# mini-rfsynth.net
KiCad netlist of a schematic drawn in Altium Designer
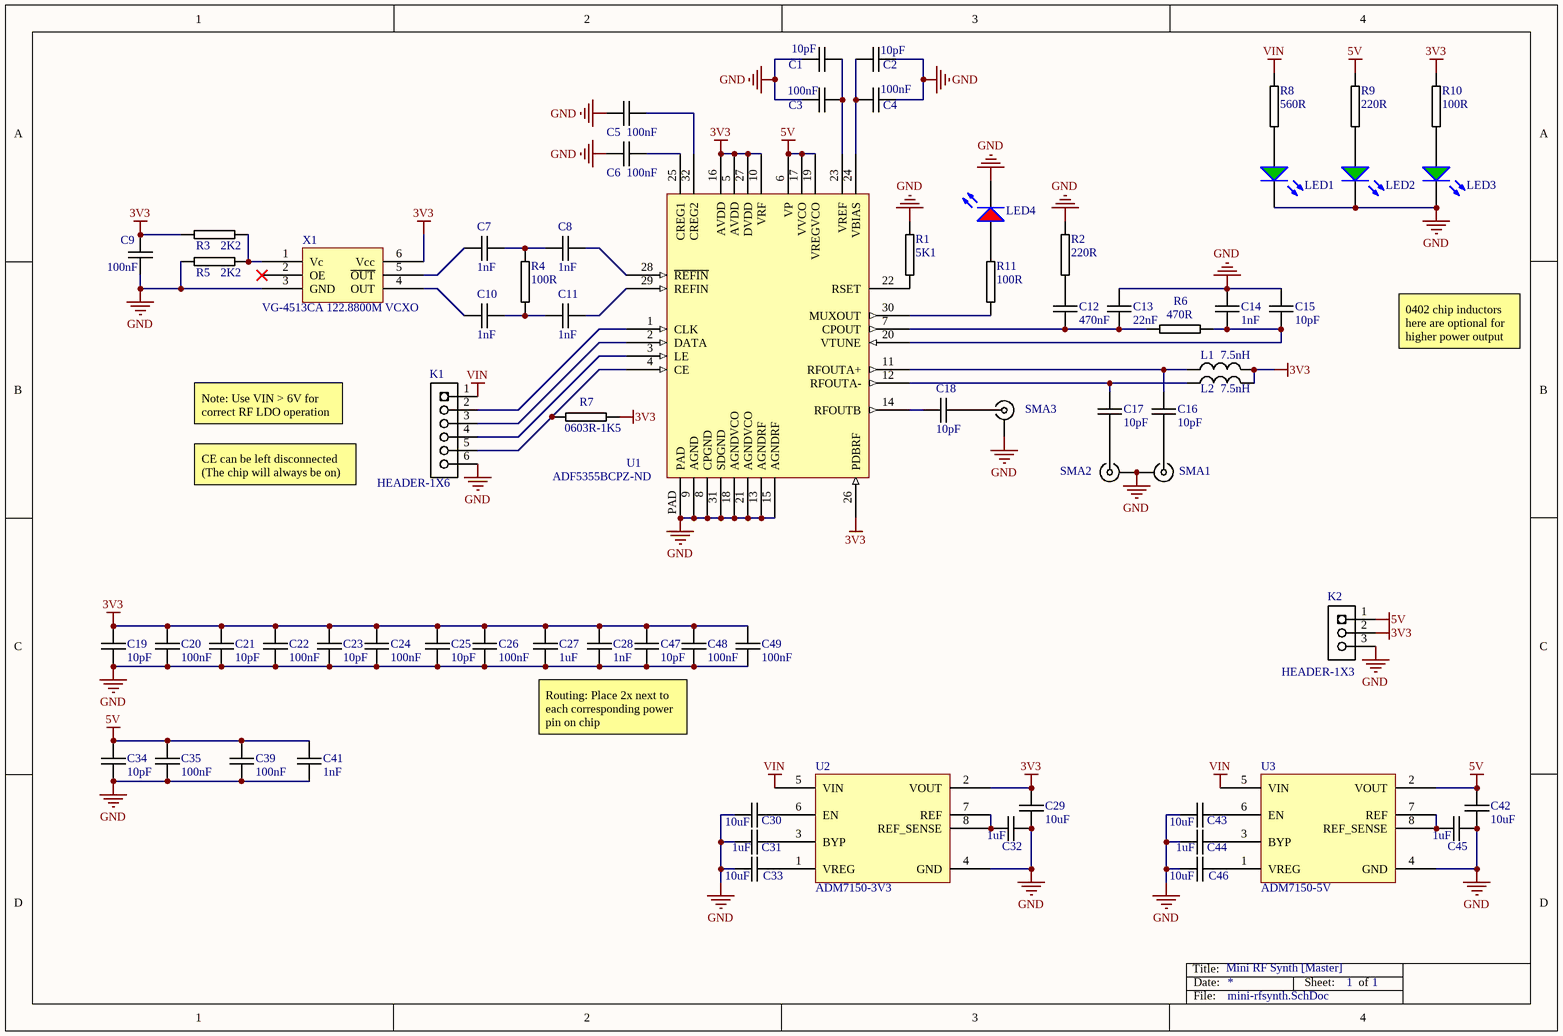
[diagram p0: mini-rfsynth.SchDoc]

(export (version "E")
  (design (tool "Eeschema 10.0.6"))
  (components
    (comp (ref "C1")
      (value "10pF")
      (footprint "0603C-GENERIC")
      (description "CAPACITOR 0603 CERAMIC")
      (libsource (lib "SMD Capacitors 0603") (part "0603C-10PF-50V-C0G-MUR"))
    )
    (comp (ref "C2")
      (value "10pF")
      (footprint "0603C-GENERIC")
      (description "CAPACITOR 0603 CERAMIC")
      (libsource (lib "SMD Capacitors 0603") (part "0603C-10PF-50V-C0G-MUR"))
    )
    (comp (ref "C3")
      (value "100nF")
      (footprint "0603C-GENERIC")
      (description "CAPACITOR 0603 CERAMIC")
      (fields (field (name "TOLERANCE") "±10%") (field (name "MANUFACTURER PART NUMBER") "C1608X7R1H103K"))
      (libsource (lib "SMD Capacitors 0603") (part "0603C-100NF-50V-X7R-TDK"))
    )
    (comp (ref "C4")
      (value "100nF")
      (footprint "0603C-GENERIC")
      (description "CAPACITOR 0603 CERAMIC")
      (fields (field (name "TOLERANCE") "±10%") (field (name "MANUFACTURER PART NUMBER") "C1608X7R1H103K"))
      (libsource (lib "SMD Capacitors 0603") (part "0603C-100NF-50V-X7R-TDK"))
    )
    (comp (ref "C5")
      (value "100nF")
      (footprint "0603C-GENERIC")
      (description "CAPACITOR 0603 CERAMIC")
      (fields (field (name "TOLERANCE") "±10%") (field (name "MANUFACTURER PART NUMBER") "C1608X7R1H103K"))
      (libsource (lib "SMD Capacitors 0603") (part "0603C-100NF-50V-X7R-TDK"))
    )
    (comp (ref "C6")
      (value "100nF")
      (footprint "0603C-GENERIC")
      (description "CAPACITOR 0603 CERAMIC")
      (fields (field (name "TOLERANCE") "±10%") (field (name "MANUFACTURER PART NUMBER") "C1608X7R1H103K"))
      (libsource (lib "SMD Capacitors 0603") (part "0603C-100NF-50V-X7R-TDK"))
    )
    (comp (ref "C7")
      (value "1nF")
      (footprint "0603C-GENERIC")
      (description "CAPACITOR 0603 CERAMIC")
      (libsource (lib "SMD Capacitors 0603") (part "0603C-1NF-50V-X7R"))
    )
    (comp (ref "C8")
      (value "1nF")
      (footprint "0603C-GENERIC")
      (description "CAPACITOR 0603 CERAMIC")
      (libsource (lib "SMD Capacitors 0603") (part "0603C-1NF-50V-X7R"))
    )
    (comp (ref "C9")
      (value "100nF")
      (footprint "0603C-GENERIC")
      (description "CAPACITOR 0603 CERAMIC")
      (fields (field (name "TOLERANCE") "±10%") (field (name "MANUFACTURER PART NUMBER") "C1608X7R1H103K"))
      (libsource (lib "SMD Capacitors 0603") (part "0603C-100NF-50V-X7R-TDK"))
    )
    (comp (ref "C10")
      (value "1nF")
      (footprint "0603C-GENERIC")
      (description "CAPACITOR 0603 CERAMIC")
      (libsource (lib "SMD Capacitors 0603") (part "0603C-1NF-50V-X7R"))
    )
    (comp (ref "C11")
      (value "1nF")
      (footprint "0603C-GENERIC")
      (description "CAPACITOR 0603 CERAMIC")
      (libsource (lib "SMD Capacitors 0603") (part "0603C-1NF-50V-X7R"))
    )
    (comp (ref "C12")
      (value "470nF")
      (footprint "0603C-GENERIC")
      (description "CAPACITOR 0603 CERAMIC")
      (fields
        (field (name "MANUFACTURER") "Murata Electronics North America")
        (field (name "TOLERANCE") "±10%")
      )
      (libsource (lib "SMD Capacitors 0603") (part "0603C-470NF-25V-X7R-MUR"))
    )
    (comp (ref "C13")
      (value "22nF")
      (footprint "0603C-GENERIC")
      (description "CAPACITOR 0603 CERAMIC")
      (libsource (lib "SMD Capacitors 0603") (part "0603C-22NF-50V-X7R-TDK"))
    )
    (comp (ref "C14")
      (value "1nF")
      (footprint "0603C-GENERIC")
      (description "CAPACITOR 0603 CERAMIC")
      (libsource (lib "SMD Capacitors 0603") (part "0603C-1NF-50V-X7R"))
    )
    (comp (ref "C15")
      (value "10pF")
      (footprint "0603C-GENERIC")
      (description "CAPACITOR 0603 CERAMIC")
      (libsource (lib "SMD Capacitors 0603") (part "0603C-10PF-50V-C0G-MUR"))
    )
    (comp (ref "C16")
      (value "10pF")
      (footprint "0603C-GENERIC")
      (description "CAPACITOR 0603 CERAMIC")
      (libsource (lib "SMD Capacitors 0603") (part "0603C-10PF-50V-C0G-MUR"))
    )
    (comp (ref "C17")
      (value "10pF")
      (footprint "0603C-GENERIC")
      (description "CAPACITOR 0603 CERAMIC")
      (libsource (lib "SMD Capacitors 0603") (part "0603C-10PF-50V-C0G-MUR"))
    )
    (comp (ref "C18")
      (value "10pF")
      (footprint "0603C-GENERIC")
      (description "CAPACITOR 0603 CERAMIC")
      (libsource (lib "SMD Capacitors 0603") (part "0603C-10PF-50V-C0G-MUR"))
    )
    (comp (ref "C19")
      (value "10pF")
      (footprint "0603C-GENERIC")
      (description "CAPACITOR 0603 CERAMIC")
      (libsource (lib "SMD Capacitors 0603") (part "0603C-10PF-50V-C0G-MUR"))
    )
    (comp (ref "C20")
      (value "100nF")
      (footprint "0603C-GENERIC")
      (description "CAPACITOR 0603 CERAMIC")
      (fields (field (name "TOLERANCE") "±10%") (field (name "MANUFACTURER PART NUMBER") "C1608X7R1H103K"))
      (libsource (lib "SMD Capacitors 0603") (part "0603C-100NF-50V-X7R-TDK"))
    )
    (comp (ref "C21")
      (value "10pF")
      (footprint "0603C-GENERIC")
      (description "CAPACITOR 0603 CERAMIC")
      (libsource (lib "SMD Capacitors 0603") (part "0603C-10PF-50V-C0G-MUR"))
    )
    (comp (ref "C22")
      (value "100nF")
      (footprint "0603C-GENERIC")
      (description "CAPACITOR 0603 CERAMIC")
      (fields (field (name "TOLERANCE") "±10%") (field (name "MANUFACTURER PART NUMBER") "C1608X7R1H103K"))
      (libsource (lib "SMD Capacitors 0603") (part "0603C-100NF-50V-X7R-TDK"))
    )
    (comp (ref "C23")
      (value "10pF")
      (footprint "0603C-GENERIC")
      (description "CAPACITOR 0603 CERAMIC")
      (libsource (lib "SMD Capacitors 0603") (part "0603C-10PF-50V-C0G-MUR"))
    )
    (comp (ref "C24")
      (value "100nF")
      (footprint "0603C-GENERIC")
      (description "CAPACITOR 0603 CERAMIC")
      (fields (field (name "TOLERANCE") "±10%") (field (name "MANUFACTURER PART NUMBER") "C1608X7R1H103K"))
      (libsource (lib "SMD Capacitors 0603") (part "0603C-100NF-50V-X7R-TDK"))
    )
    (comp (ref "C25")
      (value "10pF")
      (footprint "0603C-GENERIC")
      (description "CAPACITOR 0603 CERAMIC")
      (libsource (lib "SMD Capacitors 0603") (part "0603C-10PF-50V-C0G-MUR"))
    )
    (comp (ref "C26")
      (value "100nF")
      (footprint "0603C-GENERIC")
      (description "CAPACITOR 0603 CERAMIC")
      (fields (field (name "TOLERANCE") "±10%") (field (name "MANUFACTURER PART NUMBER") "C1608X7R1H103K"))
      (libsource (lib "SMD Capacitors 0603") (part "0603C-100NF-50V-X7R-TDK"))
    )
    (comp (ref "C27")
      (value "1uF")
      (footprint "0603C-GENERIC")
      (description "CAPACITOR 0603 CERAMIC")
      (fields
        (field (name "MANUFACTURER PART NUMBER") "EMK107B7105KA-T")
        (field (name "MANUFACTURER") "Taiyo Yuden")
      )
      (libsource (lib "SMD Capacitors 0603") (part "0603C-1UF-16V-X7R-TAY"))
    )
    (comp (ref "C28")
      (value "1nF")
      (footprint "0603C-GENERIC")
      (description "CAPACITOR 0603 CERAMIC")
      (libsource (lib "SMD Capacitors 0603") (part "0603C-1NF-50V-X7R"))
    )
    (comp (ref "C29")
      (value "10uF")
      (footprint "0805C-GENERIC")
      (description "CAPACITOR 0805 CERAMIC")
      (fields
        (field (name "MANUFACTURER PART NUMBER") "C2012X5R1C106M")
        (field (name "MANUFACTURER") "TDK Corporation")
      )
      (libsource (lib "SMD Capacitors 0805") (part "0805C-10UF-16V-X5R-TDK"))
    )
    (comp (ref "C30")
      (value "10uF")
      (footprint "0805C-GENERIC")
      (description "CAPACITOR 0805 CERAMIC")
      (fields
        (field (name "MANUFACTURER PART NUMBER") "C2012X5R1C106M")
        (field (name "MANUFACTURER") "TDK Corporation")
      )
      (libsource (lib "SMD Capacitors 0805") (part "0805C-10UF-16V-X5R-TDK"))
    )
    (comp (ref "C31")
      (value "1uF")
      (footprint "0603C-GENERIC")
      (description "CAPACITOR 0603 CERAMIC")
      (fields
        (field (name "MANUFACTURER PART NUMBER") "EMK107B7105KA-T")
        (field (name "MANUFACTURER") "Taiyo Yuden")
      )
      (libsource (lib "SMD Capacitors 0603") (part "0603C-1UF-16V-X7R-TAY"))
    )
    (comp (ref "C32")
      (value "1uF")
      (footprint "0603C-GENERIC")
      (description "CAPACITOR 0603 CERAMIC")
      (fields
        (field (name "MANUFACTURER PART NUMBER") "EMK107B7105KA-T")
        (field (name "MANUFACTURER") "Taiyo Yuden")
      )
      (libsource (lib "SMD Capacitors 0603") (part "0603C-1UF-16V-X7R-TAY"))
    )
    (comp (ref "C33")
      (value "10uF")
      (footprint "0805C-GENERIC")
      (description "CAPACITOR 0805 CERAMIC")
      (fields
        (field (name "MANUFACTURER PART NUMBER") "C2012X5R1C106M")
        (field (name "MANUFACTURER") "TDK Corporation")
      )
      (libsource (lib "SMD Capacitors 0805") (part "0805C-10UF-16V-X5R-TDK"))
    )
    (comp (ref "C34")
      (value "10pF")
      (footprint "0603C-GENERIC")
      (description "CAPACITOR 0603 CERAMIC")
      (libsource (lib "SMD Capacitors 0603") (part "0603C-10PF-50V-C0G-MUR"))
    )
    (comp (ref "C35")
      (value "100nF")
      (footprint "0603C-GENERIC")
      (description "CAPACITOR 0603 CERAMIC")
      (fields (field (name "TOLERANCE") "±10%") (field (name "MANUFACTURER PART NUMBER") "C1608X7R1H103K"))
      (libsource (lib "SMD Capacitors 0603") (part "0603C-100NF-50V-X7R-TDK"))
    )
    (comp (ref "C39")
      (value "100nF")
      (footprint "0603C-GENERIC")
      (description "CAPACITOR 0603 CERAMIC")
      (fields (field (name "TOLERANCE") "±10%") (field (name "MANUFACTURER PART NUMBER") "C1608X7R1H103K"))
      (libsource (lib "SMD Capacitors 0603") (part "0603C-100NF-50V-X7R-TDK"))
    )
    (comp (ref "C41")
      (value "1nF")
      (footprint "0603C-GENERIC")
      (description "CAPACITOR 0603 CERAMIC")
      (libsource (lib "SMD Capacitors 0603") (part "0603C-1NF-50V-X7R"))
    )
    (comp (ref "C42")
      (value "10uF")
      (footprint "0805C-GENERIC")
      (description "CAPACITOR 0805 CERAMIC")
      (fields
        (field (name "MANUFACTURER PART NUMBER") "C2012X5R1C106M")
        (field (name "MANUFACTURER") "TDK Corporation")
      )
      (libsource (lib "SMD Capacitors 0805") (part "0805C-10UF-16V-X5R-TDK"))
    )
    (comp (ref "C43")
      (value "10uF")
      (footprint "0805C-GENERIC")
      (description "CAPACITOR 0805 CERAMIC")
      (fields
        (field (name "MANUFACTURER PART NUMBER") "C2012X5R1C106M")
        (field (name "MANUFACTURER") "TDK Corporation")
      )
      (libsource (lib "SMD Capacitors 0805") (part "0805C-10UF-16V-X5R-TDK"))
    )
    (comp (ref "C44")
      (value "1uF")
      (footprint "0603C-GENERIC")
      (description "CAPACITOR 0603 CERAMIC")
      (fields
        (field (name "MANUFACTURER PART NUMBER") "EMK107B7105KA-T")
        (field (name "MANUFACTURER") "Taiyo Yuden")
      )
      (libsource (lib "SMD Capacitors 0603") (part "0603C-1UF-16V-X7R-TAY"))
    )
    (comp (ref "C45")
      (value "1uF")
      (footprint "0603C-GENERIC")
      (description "CAPACITOR 0603 CERAMIC")
      (fields
        (field (name "MANUFACTURER PART NUMBER") "EMK107B7105KA-T")
        (field (name "MANUFACTURER") "Taiyo Yuden")
      )
      (libsource (lib "SMD Capacitors 0603") (part "0603C-1UF-16V-X7R-TAY"))
    )
    (comp (ref "C46")
      (value "10uF")
      (footprint "0805C-GENERIC")
      (description "CAPACITOR 0805 CERAMIC")
      (fields
        (field (name "MANUFACTURER PART NUMBER") "C2012X5R1C106M")
        (field (name "MANUFACTURER") "TDK Corporation")
      )
      (libsource (lib "SMD Capacitors 0805") (part "0805C-10UF-16V-X5R-TDK"))
    )
    (comp (ref "C47")
      (value "10pF")
      (footprint "0603C-GENERIC")
      (description "CAPACITOR 0603 CERAMIC")
      (libsource (lib "SMD Capacitors 0603") (part "0603C-10PF-50V-C0G-MUR"))
    )
    (comp (ref "C48")
      (value "100nF")
      (footprint "0603C-GENERIC")
      (description "CAPACITOR 0603 CERAMIC")
      (fields (field (name "TOLERANCE") "±10%") (field (name "MANUFACTURER PART NUMBER") "C1608X7R1H103K"))
      (libsource (lib "SMD Capacitors 0603") (part "0603C-100NF-50V-X7R-TDK"))
    )
    (comp (ref "C49")
      (value "100nF")
      (footprint "0603C-GENERIC")
      (description "CAPACITOR 0603 CERAMIC")
      (fields (field (name "TOLERANCE") "±10%") (field (name "MANUFACTURER PART NUMBER") "C1608X7R1H103K"))
      (libsource (lib "SMD Capacitors 0603") (part "0603C-100NF-50V-X7R-TDK"))
    )
    (comp (ref "K1")
      (value "HEADER-1X6")
      (footprint "HEADER-1X6")
      (libsource (lib "TH Connectors") (part "HEADER-1X6"))
    )
    (comp (ref "K2")
      (value "HEADER-1X3")
      (footprint "HEADER-1X3")
      (libsource (lib "TH Connectors") (part "HEADER-1X3"))
    )
    (comp (ref "L1")
      (value "7.5nH")
      (footprint "0402_INDUCTOR")
      (libsource (lib "rf_new") (part "7.5nH-LQW15AN7N5H00D"))
    )
    (comp (ref "L2")
      (value "7.5nH")
      (footprint "0402_INDUCTOR")
      (libsource (lib "rf_new") (part "7.5nH-LQW15AN7N5H00D"))
    )
    (comp (ref "LED1")
      (value "Green")
      (footprint "0805LED - GREEN")
      (libsource (lib "custom_parts_old") (part "0805 SMD LED - GREEN"))
    )
    (comp (ref "LED2")
      (value "Green")
      (footprint "0805LED - GREEN")
      (libsource (lib "custom_parts_old") (part "0805 SMD LED - GREEN"))
    )
    (comp (ref "LED3")
      (value "Green")
      (footprint "0805LED - GREEN")
      (libsource (lib "custom_parts_old") (part "0805 SMD LED - GREEN"))
    )
    (comp (ref "LED4")
      (value "Red")
      (footprint "0805LED - RED")
      (libsource (lib "custom_parts_old") (part "0805 SMD LED - RED"))
    )
    (comp (ref "R1")
      (value "5K1")
      (footprint "0603R-GENERIC")
      (description "GENERIC RESISTOR 0603")
      (fields (field (name "MANUFACTURER PART NUMBER") "RMCF 1/16 15K 1% R") (field (name "TOLERANCE") "±1%"))
      (libsource (lib "SMD Resistors 0603") (part "0603R-5K1"))
    )
    (comp (ref "R2")
      (value "220R")
      (footprint "0603R-220")
      (description "GENERIC RESISTOR 0603")
      (fields
        (field (name "MANUFACTURER") "Stackpole Electronics Inc")
        (field (name "MANUFACTURER PART NUMBER") "RMCF 1/16 220 1% R")
      )
      (libsource (lib "SMD Resistors 0603") (part "0603R-220"))
    )
    (comp (ref "R3")
      (value "2K2")
      (footprint "0603R-2K2")
      (description "GENERIC RESISTOR 0603")
      (fields
        (field (name "MANUFACTURER PART NUMBER") "RMC 1/16 2.2K 1% R")
        (field (name "MANUFACTURER") "Stackpole Electronics Inc")
      )
      (libsource (lib "SMD Resistors 0603") (part "0603R-2K2"))
    )
    (comp (ref "R4")
      (value "100R")
      (footprint "0603R-100")
      (description "GENERIC RESISTOR 0603")
      (fields
        (field (name "MANUFACTURER PART NUMBER") "RMCF 1/16 100 1% R")
        (field (name "MANUFACTURER") "Stackpole Electronics Inc")
      )
      (libsource (lib "SMD Resistors 0603") (part "0603R-100"))
    )
    (comp (ref "R5")
      (value "2K2")
      (footprint "0603R-2K2")
      (description "GENERIC RESISTOR 0603")
      (fields
        (field (name "MANUFACTURER PART NUMBER") "RMC 1/16 2.2K 1% R")
        (field (name "MANUFACTURER") "Stackpole Electronics Inc")
      )
      (libsource (lib "SMD Resistors 0603") (part "0603R-2K2"))
    )
    (comp (ref "R6")
      (value "470R")
      (footprint "0603R-470")
      (description "GENERIC RESISTOR 0603")
      (fields (field (name "MANUFACTURER PART NUMBER") "RMCF 1/16 470 1% R") (field (name "TOLERANCE") "±1%"))
      (libsource (lib "SMD Resistors 0603") (part "0603R-470"))
    )
    (comp (ref "R7")
      (value "0603R-1K5")
      (footprint "0603R-1k5")
      (description "GENERIC RESISTOR 0603")
      (fields (field (name "MANUFACTURER PART NUMBER") "RMCF 1/16 15K 1% R") (field (name "TOLERANCE") "±1%"))
      (libsource (lib "SMD Resistors 0603") (part "0603R-1K5"))
    )
    (comp (ref "R8")
      (value "560R")
      (footprint "0603R-560")
      (description "GENERIC RESISTOR 0603")
      (fields
        (field (name "MANUFACTURER") "Stackpole Electronics Inc")
        (field (name "MANUFACTURER PART NUMBER") "RMC 1/16 560 1% R")
      )
      (libsource (lib "SMD Resistors 0603") (part "0603R-560"))
    )
    (comp (ref "R9")
      (value "220R")
      (footprint "0603R-220")
      (description "GENERIC RESISTOR 0603")
      (fields
        (field (name "MANUFACTURER") "Stackpole Electronics Inc")
        (field (name "MANUFACTURER PART NUMBER") "RMCF 1/16 220 1% R")
      )
      (libsource (lib "SMD Resistors 0603") (part "0603R-220"))
    )
    (comp (ref "R10")
      (value "100R")
      (footprint "0603R-100")
      (description "GENERIC RESISTOR 0603")
      (fields
        (field (name "MANUFACTURER PART NUMBER") "RMCF 1/16 100 1% R")
        (field (name "MANUFACTURER") "Stackpole Electronics Inc")
      )
      (libsource (lib "SMD Resistors 0603") (part "0603R-100"))
    )
    (comp (ref "R11")
      (value "100R")
      (footprint "0603R-100")
      (description "GENERIC RESISTOR 0603")
      (fields
        (field (name "MANUFACTURER PART NUMBER") "RMCF 1/16 100 1% R")
        (field (name "MANUFACTURER") "Stackpole Electronics Inc")
      )
      (libsource (lib "SMD Resistors 0603") (part "0603R-100"))
    )
    (comp (ref "SMA1")
      (value "MOLEX_SMA_EDGE")
      (footprint "MOLEX_SMA_EDGE")
      (libsource (lib "rf_new") (part "MOLEX_SMA_EDGE"))
    )
    (comp (ref "SMA2")
      (value "MOLEX_SMA_EDGE")
      (footprint "MOLEX_SMA_EDGE")
      (libsource (lib "") (part "MOLEX_SMA_EDGE_1"))
    )
    (comp (ref "SMA3")
      (value "MOLEX_SMA_EDGE")
      (footprint "MOLEX_SMA_EDGE")
      (libsource (lib "rf_new") (part "MOLEX_SMA_EDGE"))
    )
    (comp (ref "U1")
      (value "AD5355")
      (footprint "AD5355_LFCSP32")
      (fields (field (name "SUPPLIER PART NUMBER 1") "ADF5355BCPZ-ND"))
      (libsource (lib "rf_new") (part "AD5355"))
    )
    (comp (ref "U2")
      (value "ADM7150-3V3")
      (footprint "ADM7150_SOIC8EP")
      (libsource (lib "rf_new") (part "ADM7150-3V3"))
    )
    (comp (ref "U3")
      (value "ADM7150-5V")
      (footprint "ADM7150_SOIC8EP")
      (libsource (lib "rf_new") (part "ADM7150-5V"))
    )
    (comp (ref "X1")
      (value "VG-4513CA 122.8800M VCXO")
      (footprint "VG-4513CA-VCXO")
      (libsource (lib "rf_new") (part "VG-4513CA 122.8800M VCXO"))
    )
  )
  (nets
    (net (code "1") (name "3V3") (class "Default")
      (node (ref "C19") (pin "1") (pintype "passive"))
      (node (ref "C20") (pin "1") (pintype "passive"))
      (node (ref "C21") (pin "1") (pintype "passive"))
      (node (ref "C22") (pin "1") (pintype "passive"))
      (node (ref "C23") (pin "1") (pintype "passive"))
      (node (ref "C24") (pin "1") (pintype "passive"))
      (node (ref "C25") (pin "1") (pintype "passive"))
      (node (ref "C26") (pin "1") (pintype "passive"))
      (node (ref "C27") (pin "1") (pintype "passive"))
      (node (ref "C28") (pin "1") (pintype "passive"))
      (node (ref "C29") (pin "1") (pintype "passive"))
      (node (ref "C47") (pin "1") (pintype "passive"))
      (node (ref "C48") (pin "1") (pintype "passive"))
      (node (ref "C49") (pin "1") (pintype "passive"))
      (node (ref "C9") (pin "1") (pintype "passive"))
      (node (ref "K2") (pin "2") (pintype "passive"))
      (node (ref "L1") (pin "2") (pinfunction "2_2") (pintype "passive"))
      (node (ref "L2") (pin "2") (pinfunction "2_2") (pintype "passive"))
      (node (ref "R10") (pin "1") (pintype "passive"))
      (node (ref "R3") (pin "1") (pintype "passive"))
      (node (ref "R7") (pin "2") (pintype "passive"))
      (node (ref "U1") (pin "10") (pinfunction "VRF_10") (pintype "power_in"))
      (node (ref "U1") (pin "16") (pinfunction "AVDD_16") (pintype "power_in"))
      (node (ref "U1") (pin "26") (pinfunction "PDBRF_26") (pintype "input"))
      (node (ref "U1") (pin "27") (pinfunction "DVDD_27") (pintype "power_in"))
      (node (ref "U1") (pin "5") (pinfunction "AVDD_5") (pintype "power_in"))
      (node (ref "U2") (pin "2") (pinfunction "VOUT_2") (pintype "passive"))
      (node (ref "X1") (pin "6") (pinfunction "Vcc_6") (pintype "passive"))
    )
    (net (code "2") (name "5V") (class "Default")
      (node (ref "C34") (pin "1") (pintype "passive"))
      (node (ref "C35") (pin "1") (pintype "passive"))
      (node (ref "C39") (pin "1") (pintype "passive"))
      (node (ref "C41") (pin "1") (pintype "passive"))
      (node (ref "C42") (pin "1") (pintype "passive"))
      (node (ref "K2") (pin "1") (pintype "passive"))
      (node (ref "R9") (pin "1") (pintype "passive"))
      (node (ref "U1") (pin "17") (pinfunction "VVCO_17") (pintype "power_in"))
      (node (ref "U1") (pin "19") (pinfunction "VREGVCO_19") (pintype "power_in"))
      (node (ref "U1") (pin "6") (pinfunction "VP_6") (pintype "power_in"))
      (node (ref "U3") (pin "2") (pinfunction "VOUT_2") (pintype "passive"))
    )
    (net (code "3") (name "GND") (class "Default")
      (node (ref "C1") (pin "2") (pintype "passive"))
      (node (ref "C13") (pin "1") (pintype "passive"))
      (node (ref "C14") (pin "1") (pintype "passive"))
      (node (ref "C15") (pin "1") (pintype "passive"))
      (node (ref "C19") (pin "2") (pintype "passive"))
      (node (ref "C2") (pin "2") (pintype "passive"))
      (node (ref "C20") (pin "2") (pintype "passive"))
      (node (ref "C21") (pin "2") (pintype "passive"))
      (node (ref "C22") (pin "2") (pintype "passive"))
      (node (ref "C23") (pin "2") (pintype "passive"))
      (node (ref "C24") (pin "2") (pintype "passive"))
      (node (ref "C25") (pin "2") (pintype "passive"))
      (node (ref "C26") (pin "2") (pintype "passive"))
      (node (ref "C27") (pin "2") (pintype "passive"))
      (node (ref "C28") (pin "2") (pintype "passive"))
      (node (ref "C29") (pin "2") (pintype "passive"))
      (node (ref "C3") (pin "2") (pintype "passive"))
      (node (ref "C30") (pin "1") (pintype "passive"))
      (node (ref "C31") (pin "1") (pintype "passive"))
      (node (ref "C32") (pin "1") (pintype "passive"))
      (node (ref "C33") (pin "1") (pintype "passive"))
      (node (ref "C34") (pin "2") (pintype "passive"))
      (node (ref "C35") (pin "2") (pintype "passive"))
      (node (ref "C39") (pin "2") (pintype "passive"))
      (node (ref "C4") (pin "2") (pintype "passive"))
      (node (ref "C41") (pin "2") (pintype "passive"))
      (node (ref "C42") (pin "2") (pintype "passive"))
      (node (ref "C43") (pin "1") (pintype "passive"))
      (node (ref "C44") (pin "1") (pintype "passive"))
      (node (ref "C45") (pin "1") (pintype "passive"))
      (node (ref "C46") (pin "1") (pintype "passive"))
      (node (ref "C47") (pin "2") (pintype "passive"))
      (node (ref "C48") (pin "2") (pintype "passive"))
      (node (ref "C49") (pin "2") (pintype "passive"))
      (node (ref "C5") (pin "1") (pintype "passive"))
      (node (ref "C6") (pin "1") (pintype "passive"))
      (node (ref "C9") (pin "2") (pintype "passive"))
      (node (ref "K1") (pin "6") (pintype "passive"))
      (node (ref "K2") (pin "3") (pintype "passive"))
      (node (ref "LED1") (pin "K") (pinfunction "K_K") (pintype "passive"))
      (node (ref "LED2") (pin "K") (pinfunction "K_K") (pintype "passive"))
      (node (ref "LED3") (pin "K") (pinfunction "K_K") (pintype "passive"))
      (node (ref "LED4") (pin "K") (pinfunction "K_K") (pintype "passive"))
      (node (ref "R1") (pin "2") (pintype "passive"))
      (node (ref "R2") (pin "1") (pintype "passive"))
      (node (ref "R5") (pin "1") (pintype "passive"))
      (node (ref "SMA1") (pin "2") (pinfunction "2_2") (pintype "passive"))
      (node (ref "SMA2") (pin "2") (pinfunction "2_2") (pintype "passive"))
      (node (ref "SMA3") (pin "2") (pinfunction "2_2") (pintype "passive"))
      (node (ref "U1") (pin "13") (pinfunction "AGNDRF_13") (pintype "power_in"))
      (node (ref "U1") (pin "15") (pinfunction "AGNDRF_15") (pintype "power_in"))
      (node (ref "U1") (pin "18") (pinfunction "AGNDVCO_18") (pintype "power_in"))
      (node (ref "U1") (pin "21") (pinfunction "AGNDVCO_21") (pintype "power_in"))
      (node (ref "U1") (pin "31") (pinfunction "SDGND_31") (pintype "power_in"))
      (node (ref "U1") (pin "8") (pinfunction "CPGND_8") (pintype "power_in"))
      (node (ref "U1") (pin "9") (pinfunction "AGND_9") (pintype "power_in"))
      (node (ref "U1") (pin "PAD") (pinfunction "PAD_PAD") (pintype "power_in"))
      (node (ref "U2") (pin "4") (pinfunction "GND_4") (pintype "passive"))
      (node (ref "U3") (pin "4") (pinfunction "GND_4") (pintype "passive"))
      (node (ref "X1") (pin "3") (pinfunction "GND_3") (pintype "passive"))
    )
    (net (code "4") (name "Net-(C7-Pad2)") (class "Default")
      (node (ref "C7") (pin "2") (pintype "passive"))
      (node (ref "C8") (pin "1") (pintype "passive"))
      (node (ref "R4") (pin "1") (pintype "passive"))
    )
    (net (code "5") (name "Net-(C10-Pad2)") (class "Default")
      (node (ref "C10") (pin "2") (pintype "passive"))
      (node (ref "C11") (pin "1") (pintype "passive"))
      (node (ref "R4") (pin "2") (pintype "passive"))
    )
    (net (code "6") (name "Net-(C12-Pad1)") (class "Default")
      (node (ref "C12") (pin "1") (pintype "passive"))
      (node (ref "R2") (pin "2") (pintype "passive"))
    )
    (net (code "7") (name "Net-(C16-Pad2)") (class "Default")
      (node (ref "C16") (pin "2") (pintype "passive"))
      (node (ref "SMA1") (pin "1") (pinfunction "1_1") (pintype "passive"))
    )
    (net (code "8") (name "Net-(C17-Pad2)") (class "Default")
      (node (ref "C17") (pin "2") (pintype "passive"))
      (node (ref "SMA2") (pin "1") (pinfunction "1_1") (pintype "passive"))
    )
    (net (code "9") (name "Net-(C18-Pad2)") (class "Default")
      (node (ref "C18") (pin "2") (pintype "passive"))
      (node (ref "SMA3") (pin "1") (pinfunction "1_1") (pintype "passive"))
    )
    (net (code "10") (name "Net-(LED1-PadA)") (class "Default")
      (node (ref "LED1") (pin "A") (pinfunction "A_A") (pintype "passive"))
      (node (ref "R8") (pin "2") (pintype "passive"))
    )
    (net (code "11") (name "Net-(LED2-PadA)") (class "Default")
      (node (ref "LED2") (pin "A") (pinfunction "A_A") (pintype "passive"))
      (node (ref "R9") (pin "2") (pintype "passive"))
    )
    (net (code "12") (name "Net-(LED3-PadA)") (class "Default")
      (node (ref "LED3") (pin "A") (pinfunction "A_A") (pintype "passive"))
      (node (ref "R10") (pin "2") (pintype "passive"))
    )
    (net (code "13") (name "Net-(LED4-PadA)") (class "Default")
      (node (ref "LED4") (pin "A") (pinfunction "A_A") (pintype "passive"))
      (node (ref "R11") (pin "2") (pintype "passive"))
    )
    (net (code "14") (name "Net-(U1-CE)") (class "Default")
      (node (ref "K1") (pin "5") (pintype "passive"))
      (node (ref "R7") (pin "1") (pintype "passive"))
      (node (ref "U1") (pin "4") (pinfunction "CE_4") (pintype "input"))
    )
    (net (code "15") (name "Net-(U1-CLK)") (class "Default")
      (node (ref "K1") (pin "2") (pintype "passive"))
      (node (ref "U1") (pin "1") (pinfunction "CLK_1") (pintype "input"))
    )
    (net (code "16") (name "Net-(U1-CPOUT)") (class "Default")
      (node (ref "C12") (pin "2") (pintype "passive"))
      (node (ref "C13") (pin "2") (pintype "passive"))
      (node (ref "R6") (pin "1") (pintype "passive"))
      (node (ref "U1") (pin "7") (pinfunction "CPOUT_7") (pintype "output"))
    )
    (net (code "17") (name "Net-(U1-CREG1)") (class "Default")
      (node (ref "C6") (pin "2") (pintype "passive"))
      (node (ref "U1") (pin "25") (pinfunction "CREG1_25") (pintype "passive"))
    )
    (net (code "18") (name "Net-(U1-CREG2)") (class "Default")
      (node (ref "C5") (pin "2") (pintype "passive"))
      (node (ref "U1") (pin "32") (pinfunction "CREG2_32") (pintype "power_in"))
    )
    (net (code "19") (name "Net-(U1-DATA)") (class "Default")
      (node (ref "K1") (pin "3") (pintype "passive"))
      (node (ref "U1") (pin "2") (pinfunction "DATA_2") (pintype "input"))
    )
    (net (code "20") (name "Net-(U1-LE)") (class "Default")
      (node (ref "K1") (pin "4") (pintype "passive"))
      (node (ref "U1") (pin "3") (pinfunction "LE_3") (pintype "input"))
    )
    (net (code "21") (name "Net-(U1-MUXOUT)") (class "Default")
      (node (ref "R11") (pin "1") (pintype "passive"))
      (node (ref "U1") (pin "30") (pinfunction "MUXOUT_30") (pintype "output"))
    )
    (net (code "22") (name "Net-(U1-REFIN)") (class "Default")
      (node (ref "C11") (pin "2") (pintype "passive"))
      (node (ref "U1") (pin "29") (pinfunction "REFIN_29") (pintype "input"))
    )
    (net (code "23") (name "Net-(U1-RFOUTA+)") (class "Default")
      (node (ref "C16") (pin "1") (pintype "passive"))
      (node (ref "L1") (pin "1") (pinfunction "1_1") (pintype "passive"))
      (node (ref "U1") (pin "11") (pinfunction "RFOUTA+_11") (pintype "output"))
    )
    (net (code "24") (name "Net-(U1-RFOUTA-)") (class "Default")
      (node (ref "C17") (pin "1") (pintype "passive"))
      (node (ref "L2") (pin "1") (pinfunction "1_1") (pintype "passive"))
      (node (ref "U1") (pin "12") (pinfunction "RFOUTA-_12") (pintype "output"))
    )
    (net (code "25") (name "Net-(U1-RFOUTB)") (class "Default")
      (node (ref "C18") (pin "1") (pintype "passive"))
      (node (ref "U1") (pin "14") (pinfunction "RFOUTB_14") (pintype "output"))
    )
    (net (code "26") (name "Net-(U1-RSET)") (class "Default")
      (node (ref "R1") (pin "1") (pintype "passive"))
      (node (ref "U1") (pin "22") (pinfunction "RSET_22") (pintype "passive"))
    )
    (net (code "27") (name "Net-(U1-VBIAS)") (class "Default")
      (node (ref "C2") (pin "1") (pintype "passive"))
      (node (ref "C4") (pin "1") (pintype "passive"))
      (node (ref "U1") (pin "24") (pinfunction "VBIAS_24") (pintype "power_in"))
    )
    (net (code "28") (name "Net-(U1-VREF)") (class "Default")
      (node (ref "C1") (pin "1") (pintype "passive"))
      (node (ref "C3") (pin "1") (pintype "passive"))
      (node (ref "U1") (pin "23") (pinfunction "VREF_23") (pintype "power_in"))
    )
    (net (code "29") (name "Net-(U1-VTUNE)") (class "Default")
      (node (ref "C14") (pin "2") (pintype "passive"))
      (node (ref "C15") (pin "2") (pintype "passive"))
      (node (ref "R6") (pin "2") (pintype "passive"))
      (node (ref "U1") (pin "20") (pinfunction "VTUNE_20") (pintype "input"))
    )
    (net (code "30") (name "Net-(U1-~{REFIN})") (class "Default")
      (node (ref "C8") (pin "2") (pintype "passive"))
      (node (ref "U1") (pin "28") (pinfunction "~{REFIN}_28") (pintype "input"))
    )
    (net (code "31") (name "Net-(U2-BYP)") (class "Default")
      (node (ref "C31") (pin "2") (pintype "passive"))
      (node (ref "U2") (pin "3") (pinfunction "BYP_3") (pintype "passive"))
    )
    (net (code "32") (name "Net-(U2-EN)") (class "Default")
      (node (ref "C30") (pin "2") (pintype "passive"))
      (node (ref "U2") (pin "6") (pinfunction "EN_6") (pintype "passive"))
    )
    (net (code "33") (name "Net-(U2-REF)") (class "Default")
      (node (ref "C32") (pin "2") (pintype "passive"))
      (node (ref "U2") (pin "7") (pinfunction "REF_7") (pintype "passive"))
      (node (ref "U2") (pin "8") (pinfunction "REF_SENSE_8") (pintype "passive"))
    )
    (net (code "34") (name "Net-(U2-VREG)") (class "Default")
      (node (ref "C33") (pin "2") (pintype "passive"))
      (node (ref "U2") (pin "1") (pinfunction "VREG_1") (pintype "passive"))
    )
    (net (code "35") (name "Net-(U3-BYP)") (class "Default")
      (node (ref "C44") (pin "2") (pintype "passive"))
      (node (ref "U3") (pin "3") (pinfunction "BYP_3") (pintype "passive"))
    )
    (net (code "36") (name "Net-(U3-EN)") (class "Default")
      (node (ref "C43") (pin "2") (pintype "passive"))
      (node (ref "U3") (pin "6") (pinfunction "EN_6") (pintype "passive"))
    )
    (net (code "37") (name "Net-(U3-REF)") (class "Default")
      (node (ref "C45") (pin "2") (pintype "passive"))
      (node (ref "U3") (pin "7") (pinfunction "REF_7") (pintype "passive"))
      (node (ref "U3") (pin "8") (pinfunction "REF_SENSE_8") (pintype "passive"))
    )
    (net (code "38") (name "Net-(U3-VREG)") (class "Default")
      (node (ref "C46") (pin "2") (pintype "passive"))
      (node (ref "U3") (pin "1") (pinfunction "VREG_1") (pintype "passive"))
    )
    (net (code "39") (name "Net-(X1-OUT)") (class "Default")
      (node (ref "C10") (pin "1") (pintype "passive"))
      (node (ref "X1") (pin "4") (pinfunction "OUT_4") (pintype "passive"))
    )
    (net (code "40") (name "Net-(X1-Vc)") (class "Default")
      (node (ref "R3") (pin "2") (pintype "passive"))
      (node (ref "R5") (pin "2") (pintype "passive"))
      (node (ref "X1") (pin "1") (pinfunction "Vc_1") (pintype "passive"))
    )
    (net (code "41") (name "Net-(X1-~{OUT})") (class "Default")
      (node (ref "C7") (pin "1") (pintype "passive"))
      (node (ref "X1") (pin "5") (pinfunction "~{OUT}_5") (pintype "passive"))
    )
    (net (code "42") (name "VIN") (class "Default")
      (node (ref "K1") (pin "1") (pintype "passive"))
      (node (ref "R8") (pin "1") (pintype "passive"))
      (node (ref "U2") (pin "5") (pinfunction "VIN_5") (pintype "passive"))
      (node (ref "U3") (pin "5") (pinfunction "VIN_5") (pintype "passive"))
    )
    (net (code "43") (name "unconnected-(X1-OE-Pad2)") (class "Default")
      (node (ref "X1") (pin "2") (pinfunction "OE_2") (pintype "passive+no_connect"))
    )
  )
)
